# schematic.net
KiCad netlist of a schematic drawn in EAGLE
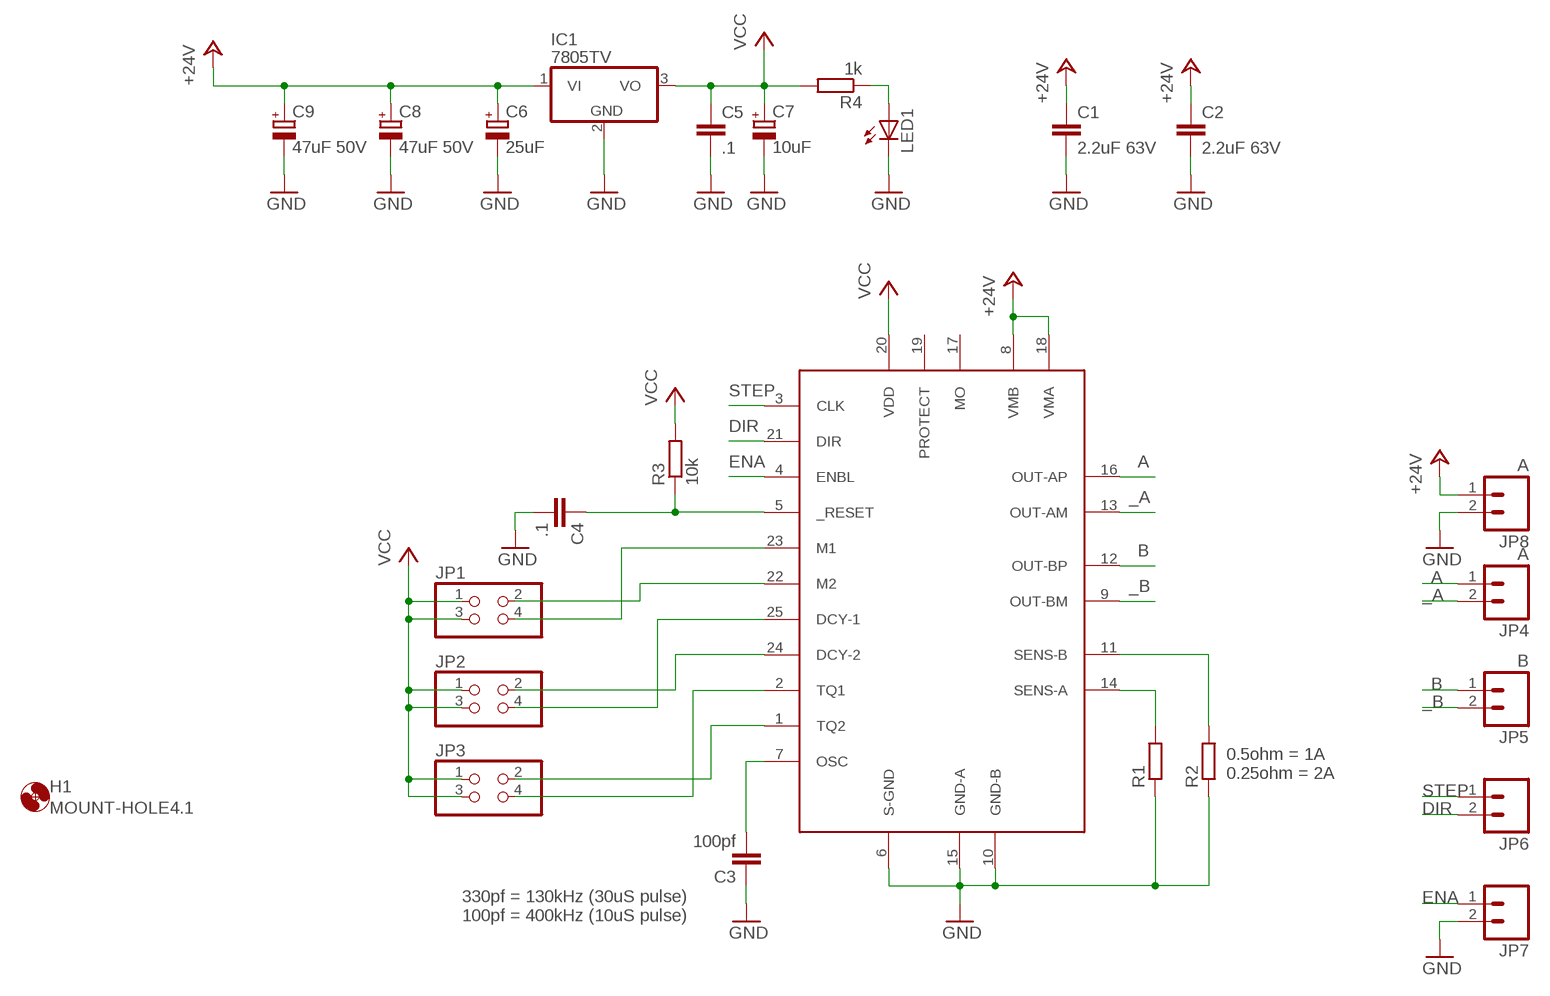
[diagram p0: schematic, sheet 1]

(export (version "E")
  (design (tool "Eeschema 10.0.6"))
  (components
    (comp (ref "C1")
      (value "2.2uF 63V")
      (footprint "eagle-import:C225-108X268")
      (libsource (lib "eagle-import") (part "C-EU225-108X268"))
    )
    (comp (ref "C2")
      (value "2.2uF 63V")
      (footprint "eagle-import:C225-108X268")
      (libsource (lib "eagle-import") (part "C-EU225-108X268"))
    )
    (comp (ref "C3")
      (value "100pf")
      (footprint "eagle-import:C0805K")
      (libsource (lib "eagle-import") (part "C-EUC0805K"))
    )
    (comp (ref "C4")
      (value ".1")
      (footprint "eagle-import:C0805K")
      (libsource (lib "eagle-import") (part "C-EUC0805K"))
    )
    (comp (ref "C5")
      (value ".1")
      (footprint "eagle-import:C0805K")
      (libsource (lib "eagle-import") (part "C-EUC0805K"))
    )
    (comp (ref "C6")
      (value "25uF")
      (footprint "eagle-import:E2,5-5")
      (libsource (lib "eagle-import") (part "CPOL-EUE2.5-5"))
    )
    (comp (ref "C7")
      (value "10uF")
      (footprint "eagle-import:E2,5-5")
      (libsource (lib "eagle-import") (part "CPOL-EUE2.5-5"))
    )
    (comp (ref "C8")
      (value "47uF 50V")
      (footprint "eagle-import:E2,5-5")
      (libsource (lib "eagle-import") (part "CPOL-EUE2.5-5"))
    )
    (comp (ref "C9")
      (value "47uF 50V")
      (footprint "eagle-import:E2,5-5")
      (libsource (lib "eagle-import") (part "CPOL-EUE2.5-5"))
    )
    (comp (ref "H1")
      (value "MOUNT-HOLE4.1")
      (footprint "eagle-import:4,1")
      (libsource (lib "eagle-import") (part "MOUNT-HOLE4.1"))
    )
    (comp (ref "IC1")
      (value "7805TV")
      (footprint "eagle-import:TO220V")
      (libsource (lib "eagle-import") (part "78TV05"))
    )
    (comp (ref "JP1")
      (value "PINHD-2X2")
      (footprint "eagle-import:2X02")
      (libsource (lib "eagle-import") (part "PINHD-2X2"))
    )
    (comp (ref "JP2")
      (value "PINHD-2X2")
      (footprint "eagle-import:2X02")
      (libsource (lib "eagle-import") (part "PINHD-2X2"))
    )
    (comp (ref "JP3")
      (value "PINHD-2X2")
      (footprint "eagle-import:2X02")
      (libsource (lib "eagle-import") (part "PINHD-2X2"))
    )
    (comp (ref "JP4")
      (value "A")
      (footprint "eagle-import:1X02_XTRA_BIG")
      (libsource (lib "eagle-import") (part "M02PTH4"))
    )
    (comp (ref "JP5")
      (value "B")
      (footprint "eagle-import:1X02_XTRA_BIG")
      (libsource (lib "eagle-import") (part "M02PTH4"))
    )
    (comp (ref "JP6")
      (value "M02POGO_PIN_HOLES_ONLY")
      (footprint "eagle-import:1X02_PP_HOLES_ONLY")
      (libsource (lib "eagle-import") (part "M02POGO_PIN_HOLES_ONLY"))
    )
    (comp (ref "JP7")
      (value "M02POGO_PIN_HOLES_ONLY")
      (footprint "eagle-import:1X02_PP_HOLES_ONLY")
      (libsource (lib "eagle-import") (part "M02POGO_PIN_HOLES_ONLY"))
    )
    (comp (ref "JP8")
      (value "A")
      (footprint "eagle-import:1X02_XTRA_BIG")
      (libsource (lib "eagle-import") (part "M02PTH4"))
    )
    (comp (ref "LED1")
      (value "TLLG4400")
      (footprint "eagle-import:LED3MM")
      (fields (field (name "MF") "VISHAY SEMICONDUCTOR"))
      (libsource (lib "eagle-import") (part "TLLG4400"))
    )
    (comp (ref "R1")
      (value "R-EU_0617/17")
      (footprint "eagle-import:0617_17")
      (libsource (lib "eagle-import") (part "R-EU_0617/17"))
    )
    (comp (ref "R2")
      (value "R-EU_0617/17")
      (footprint "eagle-import:0617_17")
      (libsource (lib "eagle-import") (part "R-EU_0617/17"))
    )
    (comp (ref "R3")
      (value "10k")
      (footprint "eagle-import:R0805")
      (libsource (lib "eagle-import") (part "R-EU_R0805"))
    )
    (comp (ref "R4")
      (value "1k")
      (footprint "eagle-import:R0805")
      (libsource (lib "eagle-import") (part "R-EU_R0805"))
    )
    (comp (ref "U$1")
      (value "TB6560-H")
      (footprint "eagle-import:ZIP25-H")
      (libsource (lib "eagle-import") (part "TB6560-H"))
    )
  )
  (nets
    (net (code "1") (name "+24V") (class "Default")
      (node (ref "C1") (pin "1") (pinfunction "1_1") (pintype "passive"))
      (node (ref "C2") (pin "1") (pinfunction "1_1") (pintype "passive"))
      (node (ref "C6") (pin "+") (pinfunction "+_+") (pintype "passive"))
      (node (ref "C8") (pin "+") (pinfunction "+_+") (pintype "passive"))
      (node (ref "C9") (pin "+") (pinfunction "+_+") (pintype "passive"))
      (node (ref "IC1") (pin "1") (pinfunction "VI_1") (pintype "input"))
      (node (ref "JP8") (pin "1") (pinfunction "1_1") (pintype "passive"))
      (node (ref "U$1") (pin "18") (pinfunction "VMA_18") (pintype "bidirectional"))
      (node (ref "U$1") (pin "8") (pinfunction "VMB_8") (pintype "bidirectional"))
    )
    (net (code "2") (name "/A") (class "Default")
      (node (ref "JP4") (pin "1") (pinfunction "1_1") (pintype "passive"))
      (node (ref "U$1") (pin "16") (pinfunction "OUT-AP_16") (pintype "output"))
    )
    (net (code "3") (name "/B") (class "Default")
      (node (ref "JP5") (pin "1") (pinfunction "1_1") (pintype "passive"))
      (node (ref "U$1") (pin "12") (pinfunction "OUT-BP_12") (pintype "output"))
    )
    (net (code "4") (name "/DIR") (class "Default")
      (node (ref "JP6") (pin "2") (pinfunction "2_2") (pintype "passive"))
      (node (ref "U$1") (pin "21") (pinfunction "DIR_21") (pintype "bidirectional"))
    )
    (net (code "5") (name "/ENA") (class "Default")
      (node (ref "JP7") (pin "1") (pinfunction "1_1") (pintype "passive"))
      (node (ref "U$1") (pin "4") (pinfunction "ENBL_4") (pintype "bidirectional"))
    )
    (net (code "6") (name "/STEP") (class "Default")
      (node (ref "JP6") (pin "1") (pinfunction "1_1") (pintype "passive"))
      (node (ref "U$1") (pin "3") (pinfunction "CLK_3") (pintype "bidirectional"))
    )
    (net (code "7") (name "/_A") (class "Default")
      (node (ref "JP4") (pin "2") (pinfunction "2_2") (pintype "passive"))
      (node (ref "U$1") (pin "13") (pinfunction "OUT-AM_13") (pintype "output"))
    )
    (net (code "8") (name "/_B") (class "Default")
      (node (ref "JP5") (pin "2") (pinfunction "2_2") (pintype "passive"))
      (node (ref "U$1") (pin "9") (pinfunction "OUT-BM_9") (pintype "output"))
    )
    (net (code "9") (name "GND") (class "Default")
      (node (ref "C1") (pin "2") (pinfunction "2_2") (pintype "passive"))
      (node (ref "C2") (pin "2") (pinfunction "2_2") (pintype "passive"))
      (node (ref "C3") (pin "1") (pinfunction "1_1") (pintype "passive"))
      (node (ref "C4") (pin "2") (pinfunction "2_2") (pintype "passive"))
      (node (ref "C5") (pin "2") (pinfunction "2_2") (pintype "passive"))
      (node (ref "C6") (pin "-") (pinfunction "-_-") (pintype "passive"))
      (node (ref "C7") (pin "-") (pinfunction "-_-") (pintype "passive"))
      (node (ref "C8") (pin "-") (pinfunction "-_-") (pintype "passive"))
      (node (ref "C9") (pin "-") (pinfunction "-_-") (pintype "passive"))
      (node (ref "IC1") (pin "2") (pinfunction "GND_2") (pintype "passive"))
      (node (ref "JP7") (pin "2") (pinfunction "2_2") (pintype "passive"))
      (node (ref "JP8") (pin "2") (pinfunction "2_2") (pintype "passive"))
      (node (ref "LED1") (pin "K") (pinfunction "C_K") (pintype "passive"))
      (node (ref "R1") (pin "1") (pinfunction "1_1") (pintype "passive"))
      (node (ref "R2") (pin "1") (pinfunction "1_1") (pintype "passive"))
      (node (ref "U$1") (pin "10") (pinfunction "GND-B_10") (pintype "bidirectional"))
      (node (ref "U$1") (pin "15") (pinfunction "GND-A_15") (pintype "bidirectional"))
      (node (ref "U$1") (pin "6") (pinfunction "S-GND_6") (pintype "bidirectional"))
    )
    (net (code "10") (name "Net-(LED1-PadA)") (class "Default")
      (node (ref "LED1") (pin "A") (pinfunction "A_A") (pintype "passive"))
      (node (ref "R4") (pin "1") (pinfunction "1_1") (pintype "passive"))
    )
    (net (code "11") (name "Net-(U$1-DCY-1)") (class "Default")
      (node (ref "JP2") (pin "4") (pinfunction "4_4") (pintype "passive"))
      (node (ref "U$1") (pin "25") (pinfunction "DCY-1_25") (pintype "bidirectional"))
    )
    (net (code "12") (name "Net-(U$1-DCY-2)") (class "Default")
      (node (ref "JP2") (pin "2") (pinfunction "2_2") (pintype "passive"))
      (node (ref "U$1") (pin "24") (pinfunction "DCY-2_24") (pintype "bidirectional"))
    )
    (net (code "13") (name "Net-(U$1-M1)") (class "Default")
      (node (ref "JP1") (pin "4") (pinfunction "4_4") (pintype "passive"))
      (node (ref "U$1") (pin "23") (pinfunction "M1_23") (pintype "bidirectional"))
    )
    (net (code "14") (name "Net-(U$1-M2)") (class "Default")
      (node (ref "JP1") (pin "2") (pinfunction "2_2") (pintype "passive"))
      (node (ref "U$1") (pin "22") (pinfunction "M2_22") (pintype "bidirectional"))
    )
    (net (code "15") (name "Net-(U$1-OSC)") (class "Default")
      (node (ref "C3") (pin "2") (pinfunction "2_2") (pintype "passive"))
      (node (ref "U$1") (pin "7") (pinfunction "OSC_7") (pintype "bidirectional"))
    )
    (net (code "16") (name "Net-(U$1-SENS-A)") (class "Default")
      (node (ref "R1") (pin "2") (pinfunction "2_2") (pintype "passive"))
      (node (ref "U$1") (pin "14") (pinfunction "SENS-A_14") (pintype "bidirectional"))
    )
    (net (code "17") (name "Net-(U$1-SENS-B)") (class "Default")
      (node (ref "R2") (pin "2") (pinfunction "2_2") (pintype "passive"))
      (node (ref "U$1") (pin "11") (pinfunction "SENS-B_11") (pintype "bidirectional"))
    )
    (net (code "18") (name "Net-(U$1-TQ1)") (class "Default")
      (node (ref "JP3") (pin "4") (pinfunction "4_4") (pintype "passive"))
      (node (ref "U$1") (pin "2") (pinfunction "TQ1_2") (pintype "bidirectional"))
    )
    (net (code "19") (name "Net-(U$1-TQ2)") (class "Default")
      (node (ref "JP3") (pin "2") (pinfunction "2_2") (pintype "passive"))
      (node (ref "U$1") (pin "1") (pinfunction "TQ2_1") (pintype "bidirectional"))
    )
    (net (code "20") (name "Net-(U$1-_RESET)") (class "Default")
      (node (ref "C4") (pin "1") (pinfunction "1_1") (pintype "passive"))
      (node (ref "R3") (pin "1") (pinfunction "1_1") (pintype "passive"))
      (node (ref "U$1") (pin "5") (pinfunction "_RESET_5") (pintype "bidirectional"))
    )
    (net (code "21") (name "VCC") (class "Default")
      (node (ref "C5") (pin "1") (pinfunction "1_1") (pintype "passive"))
      (node (ref "C7") (pin "+") (pinfunction "+_+") (pintype "passive"))
      (node (ref "IC1") (pin "3") (pinfunction "VO_3") (pintype "passive"))
      (node (ref "JP1") (pin "1") (pinfunction "1_1") (pintype "passive"))
      (node (ref "JP1") (pin "3") (pinfunction "3_3") (pintype "passive"))
      (node (ref "JP2") (pin "1") (pinfunction "1_1") (pintype "passive"))
      (node (ref "JP2") (pin "3") (pinfunction "3_3") (pintype "passive"))
      (node (ref "JP3") (pin "1") (pinfunction "1_1") (pintype "passive"))
      (node (ref "JP3") (pin "3") (pinfunction "3_3") (pintype "passive"))
      (node (ref "R3") (pin "2") (pinfunction "2_2") (pintype "passive"))
      (node (ref "R4") (pin "2") (pinfunction "2_2") (pintype "passive"))
      (node (ref "U$1") (pin "20") (pinfunction "VDD_20") (pintype "bidirectional"))
    )
    (net (code "22") (name "unconnected-(U$1-MO-Pad17)") (class "Default")
      (node (ref "U$1") (pin "17") (pinfunction "MO_17") (pintype "bidirectional"))
    )
    (net (code "23") (name "unconnected-(U$1-PROTECT-Pad19)") (class "Default")
      (node (ref "U$1") (pin "19") (pinfunction "PROTECT_19") (pintype "bidirectional"))
    )
  )
)
